# XBee_Breakout_Board.net
KiCad netlist of a schematic drawn in EAGLE
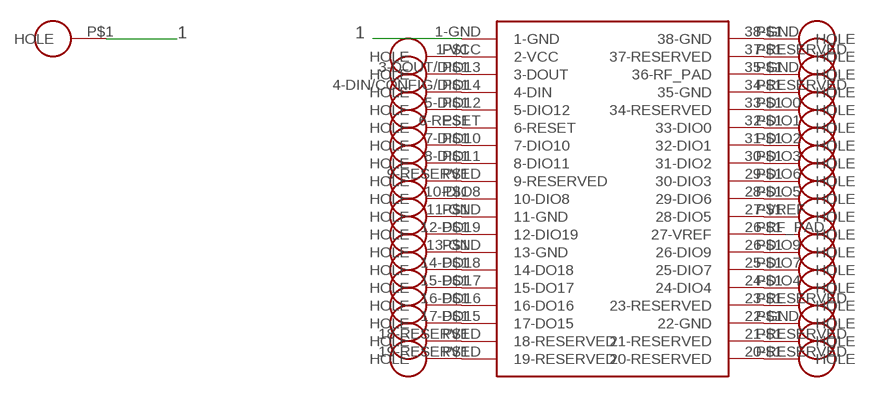
[diagram p0: schematic, sheet 1]

(export (version "E")
  (design (tool "Eeschema 10.0.6"))
  (components
    (comp (ref "U$1")
      (value "XBEE")
      (footprint "eagle-import:XBEE")
      (libsource (lib "eagle-import") (part "XBEE"))
    )
    (comp (ref "U$2")
      (value "HEADER-HOLE")
      (footprint "eagle-import:HEADER-HOLE")
      (libsource (lib "eagle-import") (part "HEADER-HOLE"))
    )
    (comp (ref "U$3")
      (value "HEADER-HOLE")
      (footprint "eagle-import:HEADER-HOLE")
      (libsource (lib "eagle-import") (part "HEADER-HOLE"))
    )
    (comp (ref "U$4")
      (value "HEADER-HOLE")
      (footprint "eagle-import:HEADER-HOLE")
      (libsource (lib "eagle-import") (part "HEADER-HOLE"))
    )
    (comp (ref "U$5")
      (value "HEADER-HOLE")
      (footprint "eagle-import:HEADER-HOLE")
      (libsource (lib "eagle-import") (part "HEADER-HOLE"))
    )
    (comp (ref "U$6")
      (value "HEADER-HOLE")
      (footprint "eagle-import:HEADER-HOLE")
      (libsource (lib "eagle-import") (part "HEADER-HOLE"))
    )
    (comp (ref "U$7")
      (value "HEADER-HOLE")
      (footprint "eagle-import:HEADER-HOLE")
      (libsource (lib "eagle-import") (part "HEADER-HOLE"))
    )
    (comp (ref "U$8")
      (value "HEADER-HOLE")
      (footprint "eagle-import:HEADER-HOLE")
      (libsource (lib "eagle-import") (part "HEADER-HOLE"))
    )
    (comp (ref "U$9")
      (value "HEADER-HOLE")
      (footprint "eagle-import:HEADER-HOLE")
      (libsource (lib "eagle-import") (part "HEADER-HOLE"))
    )
    (comp (ref "U$10")
      (value "HEADER-HOLE")
      (footprint "eagle-import:HEADER-HOLE")
      (libsource (lib "eagle-import") (part "HEADER-HOLE"))
    )
    (comp (ref "U$11")
      (value "HEADER-HOLE")
      (footprint "eagle-import:HEADER-HOLE")
      (libsource (lib "eagle-import") (part "HEADER-HOLE"))
    )
    (comp (ref "U$12")
      (value "HEADER-HOLE")
      (footprint "eagle-import:HEADER-HOLE")
      (libsource (lib "eagle-import") (part "HEADER-HOLE"))
    )
    (comp (ref "U$13")
      (value "HEADER-HOLE")
      (footprint "eagle-import:HEADER-HOLE")
      (libsource (lib "eagle-import") (part "HEADER-HOLE"))
    )
    (comp (ref "U$14")
      (value "HEADER-HOLE")
      (footprint "eagle-import:HEADER-HOLE")
      (libsource (lib "eagle-import") (part "HEADER-HOLE"))
    )
    (comp (ref "U$15")
      (value "HEADER-HOLE")
      (footprint "eagle-import:HEADER-HOLE")
      (libsource (lib "eagle-import") (part "HEADER-HOLE"))
    )
    (comp (ref "U$16")
      (value "HEADER-HOLE")
      (footprint "eagle-import:HEADER-HOLE")
      (libsource (lib "eagle-import") (part "HEADER-HOLE"))
    )
    (comp (ref "U$17")
      (value "HEADER-HOLE")
      (footprint "eagle-import:HEADER-HOLE")
      (libsource (lib "eagle-import") (part "HEADER-HOLE"))
    )
    (comp (ref "U$18")
      (value "HEADER-HOLE")
      (footprint "eagle-import:HEADER-HOLE")
      (libsource (lib "eagle-import") (part "HEADER-HOLE"))
    )
    (comp (ref "U$19")
      (value "HEADER-HOLE")
      (footprint "eagle-import:HEADER-HOLE")
      (libsource (lib "eagle-import") (part "HEADER-HOLE"))
    )
    (comp (ref "U$20")
      (value "HEADER-HOLE")
      (footprint "eagle-import:HEADER-HOLE")
      (libsource (lib "eagle-import") (part "HEADER-HOLE"))
    )
    (comp (ref "U$21")
      (value "HEADER-HOLE")
      (footprint "eagle-import:HEADER-HOLE")
      (libsource (lib "eagle-import") (part "HEADER-HOLE"))
    )
    (comp (ref "U$22")
      (value "HEADER-HOLE")
      (footprint "eagle-import:HEADER-HOLE")
      (libsource (lib "eagle-import") (part "HEADER-HOLE"))
    )
    (comp (ref "U$23")
      (value "HEADER-HOLE")
      (footprint "eagle-import:HEADER-HOLE")
      (libsource (lib "eagle-import") (part "HEADER-HOLE"))
    )
    (comp (ref "U$24")
      (value "HEADER-HOLE")
      (footprint "eagle-import:HEADER-HOLE")
      (libsource (lib "eagle-import") (part "HEADER-HOLE"))
    )
    (comp (ref "U$25")
      (value "HEADER-HOLE")
      (footprint "eagle-import:HEADER-HOLE")
      (libsource (lib "eagle-import") (part "HEADER-HOLE"))
    )
    (comp (ref "U$26")
      (value "HEADER-HOLE")
      (footprint "eagle-import:HEADER-HOLE")
      (libsource (lib "eagle-import") (part "HEADER-HOLE"))
    )
    (comp (ref "U$27")
      (value "HEADER-HOLE")
      (footprint "eagle-import:HEADER-HOLE")
      (libsource (lib "eagle-import") (part "HEADER-HOLE"))
    )
    (comp (ref "U$28")
      (value "HEADER-HOLE")
      (footprint "eagle-import:HEADER-HOLE")
      (libsource (lib "eagle-import") (part "HEADER-HOLE"))
    )
    (comp (ref "U$29")
      (value "HEADER-HOLE")
      (footprint "eagle-import:HEADER-HOLE")
      (libsource (lib "eagle-import") (part "HEADER-HOLE"))
    )
    (comp (ref "U$30")
      (value "HEADER-HOLE")
      (footprint "eagle-import:HEADER-HOLE")
      (libsource (lib "eagle-import") (part "HEADER-HOLE"))
    )
    (comp (ref "U$31")
      (value "HEADER-HOLE")
      (footprint "eagle-import:HEADER-HOLE")
      (libsource (lib "eagle-import") (part "HEADER-HOLE"))
    )
    (comp (ref "U$32")
      (value "HEADER-HOLE")
      (footprint "eagle-import:HEADER-HOLE")
      (libsource (lib "eagle-import") (part "HEADER-HOLE"))
    )
    (comp (ref "U$33")
      (value "HEADER-HOLE")
      (footprint "eagle-import:HEADER-HOLE")
      (libsource (lib "eagle-import") (part "HEADER-HOLE"))
    )
    (comp (ref "U$34")
      (value "HEADER-HOLE")
      (footprint "eagle-import:HEADER-HOLE")
      (libsource (lib "eagle-import") (part "HEADER-HOLE"))
    )
    (comp (ref "U$35")
      (value "HEADER-HOLE")
      (footprint "eagle-import:HEADER-HOLE")
      (libsource (lib "eagle-import") (part "HEADER-HOLE"))
    )
    (comp (ref "U$36")
      (value "HEADER-HOLE")
      (footprint "eagle-import:HEADER-HOLE")
      (libsource (lib "eagle-import") (part "HEADER-HOLE"))
    )
    (comp (ref "U$37")
      (value "HEADER-HOLE")
      (footprint "eagle-import:HEADER-HOLE")
      (libsource (lib "eagle-import") (part "HEADER-HOLE"))
    )
    (comp (ref "U$38")
      (value "HEADER-HOLE")
      (footprint "eagle-import:HEADER-HOLE")
      (libsource (lib "eagle-import") (part "HEADER-HOLE"))
    )
    (comp (ref "U$39")
      (value "HEADER-HOLE")
      (footprint "eagle-import:HEADER-HOLE")
      (libsource (lib "eagle-import") (part "HEADER-HOLE"))
    )
  )
  (nets
    (net (code "1") (name "/1") (class "Default")
      (node (ref "U$1") (pin "1-GND") (pinfunction "1-GND_1-GND") (pintype "bidirectional"))
      (node (ref "U$2") (pin "P$1") (pinfunction "HOLE_P$1") (pintype "bidirectional"))
    )
    (net (code "2") (name "Net-(U$1-2-VCC)") (class "Default")
      (node (ref "U$1") (pin "1-VCC") (pinfunction "2-VCC_1-VCC") (pintype "bidirectional"))
      (node (ref "U$3") (pin "P$1") (pinfunction "HOLE_P$1") (pintype "bidirectional"))
    )
    (net (code "3") (name "Net-(U$1-3-DOUT)") (class "Default")
      (node (ref "U$1") (pin "3-DOUT/DIO13") (pinfunction "3-DOUT_3-DOUT/DIO13") (pintype "bidirectional"))
      (node (ref "U$4") (pin "P$1") (pinfunction "HOLE_P$1") (pintype "bidirectional"))
    )
    (net (code "4") (name "Net-(U$1-4-DIN)") (class "Default")
      (node (ref "U$1") (pin "4-DIN/CONFIG/DIO14") (pinfunction "4-DIN_4-DIN/CONFIG/DIO14") (pintype "bidirectional"))
      (node (ref "U$5") (pin "P$1") (pinfunction "HOLE_P$1") (pintype "bidirectional"))
    )
    (net (code "5") (name "Net-(U$1-12-DIO19)") (class "Default")
      (node (ref "U$1") (pin "12-DO19") (pinfunction "12-DIO19_12-DO19") (pintype "bidirectional"))
      (node (ref "U$13") (pin "P$1") (pinfunction "HOLE_P$1") (pintype "bidirectional"))
    )
    (net (code "6") (name "Net-(U$1-27-VREF)") (class "Default")
      (node (ref "U$1") (pin "26-RF_PAD") (pinfunction "27-VREF_26-RF_PAD") (pintype "bidirectional"))
      (node (ref "U$32") (pin "P$1") (pinfunction "HOLE_P$1") (pintype "bidirectional"))
    )
    (net (code "7") (name "Net-(U$1-28-DIO5)") (class "Default")
      (node (ref "U$1") (pin "27-VREF") (pinfunction "28-DIO5_27-VREF") (pintype "bidirectional"))
      (node (ref "U$31") (pin "P$1") (pinfunction "HOLE_P$1") (pintype "bidirectional"))
    )
    (net (code "8") (name "Net-(U$1-29-DIO6)") (class "Default")
      (node (ref "U$1") (pin "28-DIO5") (pinfunction "29-DIO6_28-DIO5") (pintype "bidirectional"))
      (node (ref "U$30") (pin "P$1") (pinfunction "HOLE_P$1") (pintype "bidirectional"))
    )
    (net (code "9") (name "Net-(U$1-30-DIO3)") (class "Default")
      (node (ref "U$1") (pin "29-DIO6") (pinfunction "30-DIO3_29-DIO6") (pintype "bidirectional"))
      (node (ref "U$29") (pin "P$1") (pinfunction "HOLE_P$1") (pintype "bidirectional"))
    )
    (net (code "10") (name "Net-(U$1-31-DIO2)") (class "Default")
      (node (ref "U$1") (pin "30-DIO3") (pinfunction "31-DIO2_30-DIO3") (pintype "bidirectional"))
      (node (ref "U$28") (pin "P$1") (pinfunction "HOLE_P$1") (pintype "bidirectional"))
    )
    (net (code "11") (name "Net-(U$1-32-DIO1)") (class "Default")
      (node (ref "U$1") (pin "31-DIO2") (pinfunction "32-DIO1_31-DIO2") (pintype "bidirectional"))
      (node (ref "U$27") (pin "P$1") (pinfunction "HOLE_P$1") (pintype "bidirectional"))
    )
    (net (code "12") (name "Net-(U$1-33-DIO0)") (class "Default")
      (node (ref "U$1") (pin "32-DIO1") (pinfunction "33-DIO0_32-DIO1") (pintype "bidirectional"))
      (node (ref "U$26") (pin "P$1") (pinfunction "HOLE_P$1") (pintype "bidirectional"))
    )
    (net (code "13") (name "Net-(U$1-34-RESERVED)") (class "Default")
      (node (ref "U$1") (pin "33-DIO0") (pinfunction "34-RESERVED_33-DIO0") (pintype "bidirectional"))
      (node (ref "U$25") (pin "P$1") (pinfunction "HOLE_P$1") (pintype "bidirectional"))
    )
    (net (code "14") (name "Net-(U$1-35-GND)") (class "Default")
      (node (ref "U$1") (pin "34-RESERVED") (pinfunction "35-GND_34-RESERVED") (pintype "bidirectional"))
      (node (ref "U$24") (pin "P$1") (pinfunction "HOLE_P$1") (pintype "bidirectional"))
    )
    (net (code "15") (name "Net-(U$1-36-RF_PAD)") (class "Default")
      (node (ref "U$1") (pin "35-GND") (pinfunction "36-RF_PAD_35-GND") (pintype "bidirectional"))
      (node (ref "U$23") (pin "P$1") (pinfunction "HOLE_P$1") (pintype "bidirectional"))
    )
    (net (code "16") (name "Net-(U$6-HOLE)") (class "Default")
      (node (ref "U$1") (pin "5-DIO12") (pinfunction "5-DIO12_5-DIO12") (pintype "bidirectional"))
      (node (ref "U$6") (pin "P$1") (pinfunction "HOLE_P$1") (pintype "bidirectional"))
    )
    (net (code "17") (name "Net-(U$7-HOLE)") (class "Default")
      (node (ref "U$1") (pin "6-RESET") (pinfunction "6-RESET_6-RESET") (pintype "bidirectional"))
      (node (ref "U$7") (pin "P$1") (pinfunction "HOLE_P$1") (pintype "bidirectional"))
    )
    (net (code "18") (name "Net-(U$8-HOLE)") (class "Default")
      (node (ref "U$1") (pin "7-DIO10") (pinfunction "7-DIO10_7-DIO10") (pintype "bidirectional"))
      (node (ref "U$8") (pin "P$1") (pinfunction "HOLE_P$1") (pintype "bidirectional"))
    )
    (net (code "19") (name "Net-(U$9-HOLE)") (class "Default")
      (node (ref "U$1") (pin "8-DIO11") (pinfunction "8-DIO11_8-DIO11") (pintype "bidirectional"))
      (node (ref "U$9") (pin "P$1") (pinfunction "HOLE_P$1") (pintype "bidirectional"))
    )
    (net (code "20") (name "Net-(U$10-HOLE)") (class "Default")
      (node (ref "U$1") (pin "9-RESERVED") (pinfunction "9-RESERVED_9-RESERVED") (pintype "bidirectional"))
      (node (ref "U$10") (pin "P$1") (pinfunction "HOLE_P$1") (pintype "bidirectional"))
    )
    (net (code "21") (name "Net-(U$11-HOLE)") (class "Default")
      (node (ref "U$1") (pin "10-DIO8") (pinfunction "10-DIO8_10-DIO8") (pintype "bidirectional"))
      (node (ref "U$11") (pin "P$1") (pinfunction "HOLE_P$1") (pintype "bidirectional"))
    )
    (net (code "22") (name "Net-(U$12-HOLE)") (class "Default")
      (node (ref "U$1") (pin "11-GND") (pinfunction "11-GND_11-GND") (pintype "bidirectional"))
      (node (ref "U$12") (pin "P$1") (pinfunction "HOLE_P$1") (pintype "bidirectional"))
    )
    (net (code "23") (name "Net-(U$14-HOLE)") (class "Default")
      (node (ref "U$1") (pin "13-GND") (pinfunction "13-GND_13-GND") (pintype "bidirectional"))
      (node (ref "U$14") (pin "P$1") (pinfunction "HOLE_P$1") (pintype "bidirectional"))
    )
    (net (code "24") (name "Net-(U$15-HOLE)") (class "Default")
      (node (ref "U$1") (pin "14-DO18") (pinfunction "14-DO18_14-DO18") (pintype "bidirectional"))
      (node (ref "U$15") (pin "P$1") (pinfunction "HOLE_P$1") (pintype "bidirectional"))
    )
    (net (code "25") (name "Net-(U$16-HOLE)") (class "Default")
      (node (ref "U$1") (pin "15-DO17") (pinfunction "15-DO17_15-DO17") (pintype "bidirectional"))
      (node (ref "U$16") (pin "P$1") (pinfunction "HOLE_P$1") (pintype "bidirectional"))
    )
    (net (code "26") (name "Net-(U$17-HOLE)") (class "Default")
      (node (ref "U$1") (pin "16-DO16") (pinfunction "16-DO16_16-DO16") (pintype "bidirectional"))
      (node (ref "U$17") (pin "P$1") (pinfunction "HOLE_P$1") (pintype "bidirectional"))
    )
    (net (code "27") (name "Net-(U$18-HOLE)") (class "Default")
      (node (ref "U$1") (pin "17-DO15") (pinfunction "17-DO15_17-DO15") (pintype "bidirectional"))
      (node (ref "U$18") (pin "P$1") (pinfunction "HOLE_P$1") (pintype "bidirectional"))
    )
    (net (code "28") (name "Net-(U$19-HOLE)") (class "Default")
      (node (ref "U$1") (pin "18-RESERVED") (pinfunction "18-RESERVED_18-RESERVED") (pintype "bidirectional"))
      (node (ref "U$19") (pin "P$1") (pinfunction "HOLE_P$1") (pintype "bidirectional"))
    )
    (net (code "29") (name "Net-(U$20-HOLE)") (class "Default")
      (node (ref "U$1") (pin "19-RESERVED") (pinfunction "19-RESERVED_19-RESERVED") (pintype "bidirectional"))
      (node (ref "U$20") (pin "P$1") (pinfunction "HOLE_P$1") (pintype "bidirectional"))
    )
    (net (code "30") (name "Net-(U$21-HOLE)") (class "Default")
      (node (ref "U$1") (pin "38-GND") (pinfunction "38-GND_38-GND") (pintype "bidirectional"))
      (node (ref "U$21") (pin "P$1") (pinfunction "HOLE_P$1") (pintype "bidirectional"))
    )
    (net (code "31") (name "Net-(U$22-HOLE)") (class "Default")
      (node (ref "U$1") (pin "37-RESERVED") (pinfunction "37-RESERVED_37-RESERVED") (pintype "bidirectional"))
      (node (ref "U$22") (pin "P$1") (pinfunction "HOLE_P$1") (pintype "bidirectional"))
    )
    (net (code "32") (name "Net-(U$33-HOLE)") (class "Default")
      (node (ref "U$1") (pin "26-DIO9") (pinfunction "26-DIO9_26-DIO9") (pintype "bidirectional"))
      (node (ref "U$33") (pin "P$1") (pinfunction "HOLE_P$1") (pintype "bidirectional"))
    )
    (net (code "33") (name "Net-(U$34-HOLE)") (class "Default")
      (node (ref "U$1") (pin "25-DIO7") (pinfunction "25-DIO7_25-DIO7") (pintype "bidirectional"))
      (node (ref "U$34") (pin "P$1") (pinfunction "HOLE_P$1") (pintype "bidirectional"))
    )
    (net (code "34") (name "Net-(U$35-HOLE)") (class "Default")
      (node (ref "U$1") (pin "23-RESERVED") (pinfunction "23-RESERVED_23-RESERVED") (pintype "bidirectional"))
      (node (ref "U$35") (pin "P$1") (pinfunction "HOLE_P$1") (pintype "bidirectional"))
    )
    (net (code "35") (name "Net-(U$36-HOLE)") (class "Default")
      (node (ref "U$1") (pin "24-DIO4") (pinfunction "24-DIO4_24-DIO4") (pintype "bidirectional"))
      (node (ref "U$36") (pin "P$1") (pinfunction "HOLE_P$1") (pintype "bidirectional"))
    )
    (net (code "36") (name "Net-(U$37-HOLE)") (class "Default")
      (node (ref "U$1") (pin "21-RESERVED") (pinfunction "21-RESERVED_21-RESERVED") (pintype "bidirectional"))
      (node (ref "U$37") (pin "P$1") (pinfunction "HOLE_P$1") (pintype "bidirectional"))
    )
    (net (code "37") (name "Net-(U$38-HOLE)") (class "Default")
      (node (ref "U$1") (pin "22-GND") (pinfunction "22-GND_22-GND") (pintype "bidirectional"))
      (node (ref "U$38") (pin "P$1") (pinfunction "HOLE_P$1") (pintype "bidirectional"))
    )
    (net (code "38") (name "Net-(U$39-HOLE)") (class "Default")
      (node (ref "U$1") (pin "20-RESERVED") (pinfunction "20-RESERVED_20-RESERVED") (pintype "bidirectional"))
      (node (ref "U$39") (pin "P$1") (pinfunction "HOLE_P$1") (pintype "bidirectional"))
    )
  )
)
